# FR4_Wilkinson_Divider.net
KiCad netlist of a schematic drawn in Altium Designer
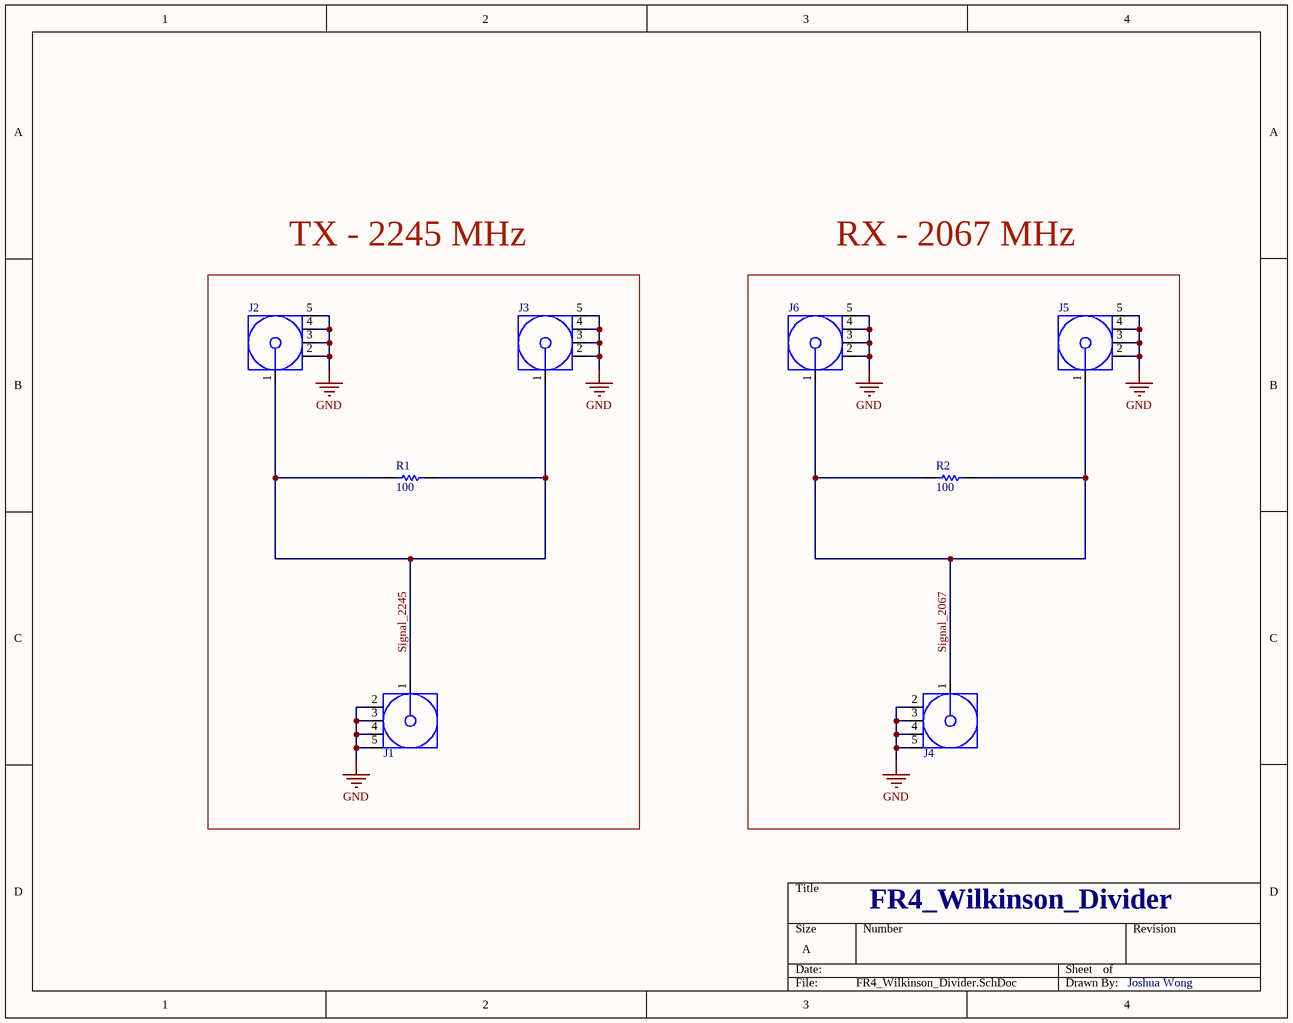
[diagram p0: FR4_Wilkinson_Divider.SchDoc]

(export (version "E")
  (design (tool "Eeschema 10.0.6"))
  (components
    (comp (ref "J1")
      (value "0732511150")
      (footprint "FP-0732511150-MFG")
      (description "RF SMA Connector, 1 Contact(s), Board Mount, Surface Mount Terminal, Locking")
      (libsource (lib "University of Toronto Aerospace Team") (part "COAX-F"))
    )
    (comp (ref "J2")
      (value "0732511150")
      (footprint "FP-0732511150-MFG")
      (description "RF SMA Connector, 1 Contact(s), Board Mount, Surface Mount Terminal, Locking")
      (libsource (lib "University of Toronto Aerospace Team") (part "COAX-F"))
    )
    (comp (ref "J3")
      (value "0732511150")
      (footprint "FP-0732511150-MFG")
      (description "RF SMA Connector, 1 Contact(s), Board Mount, Surface Mount Terminal, Locking")
      (libsource (lib "University of Toronto Aerospace Team") (part "COAX-F"))
    )
    (comp (ref "J4")
      (value "0732511150")
      (footprint "FP-0732511150-MFG")
      (description "RF SMA Connector, 1 Contact(s), Board Mount, Surface Mount Terminal, Locking")
      (libsource (lib "University of Toronto Aerospace Team") (part "COAX-F"))
    )
    (comp (ref "J5")
      (value "0732511150")
      (footprint "FP-0732511150-MFG")
      (description "RF SMA Connector, 1 Contact(s), Board Mount, Surface Mount Terminal, Locking")
      (libsource (lib "University of Toronto Aerospace Team") (part "COAX-F"))
    )
    (comp (ref "J6")
      (value "0732511150")
      (footprint "FP-0732511150-MFG")
      (description "RF SMA Connector, 1 Contact(s), Board Mount, Surface Mount Terminal, Locking")
      (libsource (lib "University of Toronto Aerospace Team") (part "COAX-F"))
    )
    (comp (ref "R1")
      (value "100")
      (footprint "RES0402R")
      (description "RES SMD 100 OHM 1% 1/16W 0402")
      (fields (field (name "MANUFACTURER") "Vishay Dale") (field (name "TOLERANCE") "1%"))
      (libsource (lib "University of Toronto Aerospace Team") (part "Res-2"))
    )
    (comp (ref "R2")
      (value "100")
      (footprint "RES0402R")
      (description "RES SMD 100 OHM 1% 1/16W 0402")
      (fields (field (name "MANUFACTURER") "Vishay Dale") (field (name "TOLERANCE") "1%"))
      (libsource (lib "University of Toronto Aerospace Team") (part "Res-2"))
    )
  )
  (nets
    (net (code "1") (name "/Signal_2067") (class "Default")
      (node (ref "J4") (pin "1") (pinfunction "Signal_1") (pintype "passive"))
      (node (ref "J5") (pin "1") (pinfunction "Signal_1") (pintype "passive"))
      (node (ref "J6") (pin "1") (pinfunction "Signal_1") (pintype "passive"))
      (node (ref "R2") (pin "1") (pinfunction "1_1") (pintype "passive"))
      (node (ref "R2") (pin "2") (pinfunction "2_2") (pintype "passive"))
    )
    (net (code "2") (name "/Signal_2245") (class "Default")
      (node (ref "J1") (pin "1") (pinfunction "Signal_1") (pintype "passive"))
      (node (ref "J2") (pin "1") (pinfunction "Signal_1") (pintype "passive"))
      (node (ref "J3") (pin "1") (pinfunction "Signal_1") (pintype "passive"))
      (node (ref "R1") (pin "1") (pinfunction "1_1") (pintype "passive"))
      (node (ref "R1") (pin "2") (pinfunction "2_2") (pintype "passive"))
    )
    (net (code "3") (name "GND") (class "Default")
      (node (ref "J1") (pin "2") (pinfunction "GND_2") (pintype "power_in"))
      (node (ref "J1") (pin "3") (pinfunction "GND_3") (pintype "power_in"))
      (node (ref "J1") (pin "4") (pinfunction "GND_4") (pintype "power_in"))
      (node (ref "J1") (pin "5") (pinfunction "GND_5") (pintype "power_in"))
      (node (ref "J2") (pin "2") (pinfunction "GND_2") (pintype "power_in"))
      (node (ref "J2") (pin "3") (pinfunction "GND_3") (pintype "power_in"))
      (node (ref "J2") (pin "4") (pinfunction "GND_4") (pintype "power_in"))
      (node (ref "J2") (pin "5") (pinfunction "GND_5") (pintype "power_in"))
      (node (ref "J3") (pin "2") (pinfunction "GND_2") (pintype "power_in"))
      (node (ref "J3") (pin "3") (pinfunction "GND_3") (pintype "power_in"))
      (node (ref "J3") (pin "4") (pinfunction "GND_4") (pintype "power_in"))
      (node (ref "J3") (pin "5") (pinfunction "GND_5") (pintype "power_in"))
      (node (ref "J4") (pin "2") (pinfunction "GND_2") (pintype "power_in"))
      (node (ref "J4") (pin "3") (pinfunction "GND_3") (pintype "power_in"))
      (node (ref "J4") (pin "4") (pinfunction "GND_4") (pintype "power_in"))
      (node (ref "J4") (pin "5") (pinfunction "GND_5") (pintype "power_in"))
      (node (ref "J5") (pin "2") (pinfunction "GND_2") (pintype "power_in"))
      (node (ref "J5") (pin "3") (pinfunction "GND_3") (pintype "power_in"))
      (node (ref "J5") (pin "4") (pinfunction "GND_4") (pintype "power_in"))
      (node (ref "J5") (pin "5") (pinfunction "GND_5") (pintype "power_in"))
      (node (ref "J6") (pin "2") (pinfunction "GND_2") (pintype "power_in"))
      (node (ref "J6") (pin "3") (pinfunction "GND_3") (pintype "power_in"))
      (node (ref "J6") (pin "4") (pinfunction "GND_4") (pintype "power_in"))
      (node (ref "J6") (pin "5") (pinfunction "GND_5") (pintype "power_in"))
    )
  )
)
